# MusicVis.net
KiCad netlist of a schematic drawn in EAGLE
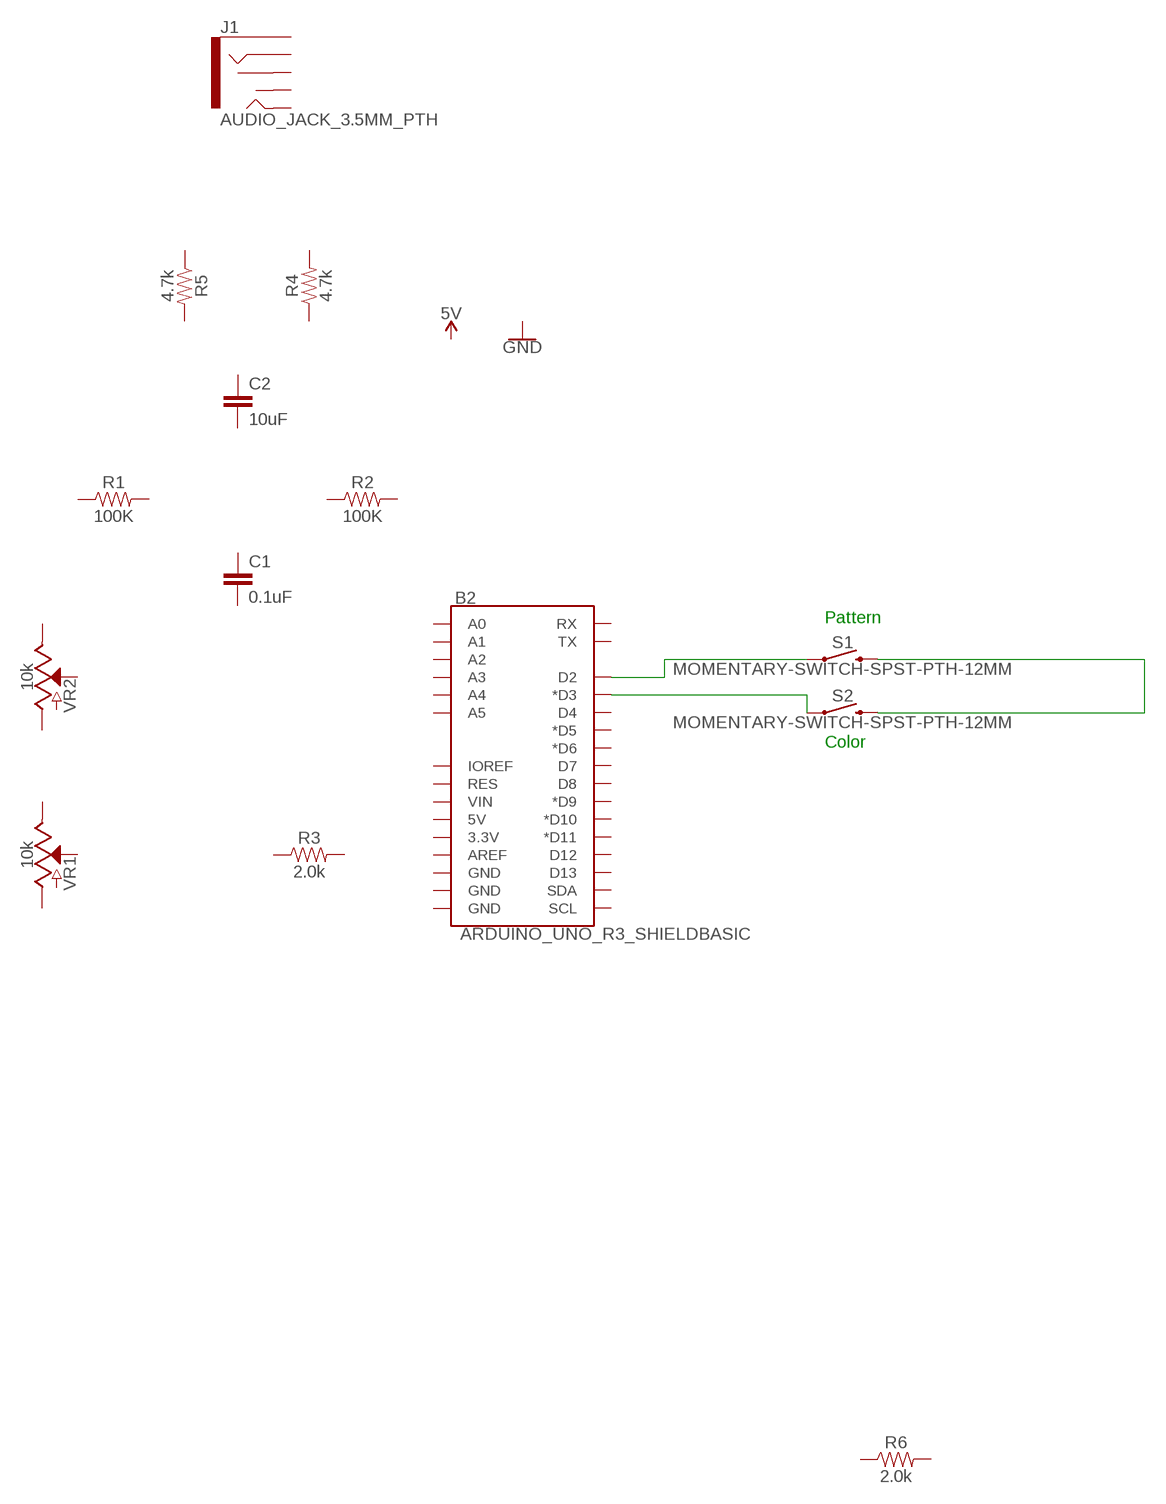
[diagram p0: schematic, sheet 1]

(export (version "E")
  (design (tool "Eeschema 10.0.6"))
  (components
    (comp (ref "B2")
      (value "ARDUINO_UNO_R3_SHIELDBASIC")
      (footprint "eagle-import:UNO_R3_SHIELD")
      (libsource (lib "eagle-import") (part "ARDUINO_UNO_R3_SHIELDBASIC"))
    )
    (comp (ref "C1")
      (value "0.1uF")
      (footprint "eagle-import:0402")
      (libsource (lib "eagle-import") (part "0.1UF-0402-16V-10%"))
    )
    (comp (ref "C2")
      (value "10uF")
      (footprint "eagle-import:0603")
      (libsource (lib "eagle-import") (part "10UF-0603-6.3V-20%"))
    )
    (comp (ref "J1")
      (value "AUDIO_JACK_3.5MM_PTH")
      (footprint "eagle-import:AUDIO-JACK")
      (libsource (lib "eagle-import") (part "AUDIO_JACK_3.5MM_PTH"))
    )
    (comp (ref "R1")
      (value "100K")
      (footprint "eagle-import:0402")
      (libsource (lib "eagle-import") (part "100KOHM-0402-1/16W-1%"))
    )
    (comp (ref "R2")
      (value "100K")
      (footprint "eagle-import:0402")
      (libsource (lib "eagle-import") (part "100KOHM-0402-1/16W-1%"))
    )
    (comp (ref "R3")
      (value "2.0k")
      (footprint "eagle-import:0603")
      (libsource (lib "eagle-import") (part "2.0KOHM-0603-1/10W-5%"))
    )
    (comp (ref "R4")
      (value "4.7k")
      (footprint "eagle-import:0603")
      (libsource (lib "eagle-import") (part "4.7KOHM-0603-1/10W-1%"))
    )
    (comp (ref "R5")
      (value "4.7k")
      (footprint "eagle-import:0603")
      (libsource (lib "eagle-import") (part "4.7KOHM-0603-1/10W-1%"))
    )
    (comp (ref "R6")
      (value "2.0k")
      (footprint "eagle-import:0603")
      (libsource (lib "eagle-import") (part "2.0KOHM-0603-1/10W-5%"))
    )
    (comp (ref "S1")
      (value "MOMENTARY-SWITCH-SPST-PTH-12MM")
      (footprint "eagle-import:TACTILE_SWITCH_PTH_12MM")
      (libsource (lib "eagle-import") (part "MOMENTARY-SWITCH-SPST-PTH-12MM"))
    )
    (comp (ref "S2")
      (value "MOMENTARY-SWITCH-SPST-PTH-12MM")
      (footprint "eagle-import:TACTILE_SWITCH_PTH_12MM")
      (libsource (lib "eagle-import") (part "MOMENTARY-SWITCH-SPST-PTH-12MM"))
    )
    (comp (ref "VR1")
      (value "10k")
      (footprint "eagle-import:POT-PTH-ALPS")
      (libsource (lib "eagle-import") (part "POTENTIOMETER-PTH-9MM-1/20W-20%"))
    )
    (comp (ref "VR2")
      (value "10k")
      (footprint "eagle-import:POT-PTH-ALPS")
      (libsource (lib "eagle-import") (part "POTENTIOMETER-PTH-9MM-1/20W-20%"))
    )
  )
  (nets
    (net (code "3") (name "Net-(B2-*D3)") (class "Default")
      (node (ref "B2") (pin "D3") (pinfunction "*D3_D3") (pintype "bidirectional"))
      (node (ref "S2") (pin "1") (pinfunction "1_1") (pintype "passive"))
    )
    (net (code "4") (name "Net-(B2-PadD2)") (class "Default")
      (node (ref "B2") (pin "D2") (pinfunction "D2_D2") (pintype "bidirectional"))
      (node (ref "S1") (pin "1") (pinfunction "1_1") (pintype "passive"))
    )
    (net (code "5") (name "Net-(S1-2)") (class "Default")
      (node (ref "S1") (pin "3") (pinfunction "2_3") (pintype "passive"))
      (node (ref "S2") (pin "3") (pinfunction "2_3") (pintype "passive"))
    )
    (net (code "6") (name "unconnected-(B2-*D5-PadD5)") (class "Default")
      (node (ref "B2") (pin "D5") (pinfunction "*D5_D5") (pintype "bidirectional"))
    )
    (net (code "7") (name "unconnected-(B2-*D6-PadD6)") (class "Default")
      (node (ref "B2") (pin "D6") (pinfunction "*D6_D6") (pintype "bidirectional"))
    )
    (net (code "8") (name "unconnected-(B2-*D9-PadD9)") (class "Default")
      (node (ref "B2") (pin "D9") (pinfunction "*D9_D9") (pintype "bidirectional"))
    )
    (net (code "9") (name "unconnected-(B2-*D10-PadD10)") (class "Default")
      (node (ref "B2") (pin "D10") (pinfunction "*D10_D10") (pintype "bidirectional"))
    )
    (net (code "10") (name "unconnected-(B2-*D11-PadD11)") (class "Default")
      (node (ref "B2") (pin "D11") (pinfunction "*D11_D11") (pintype "bidirectional"))
    )
    (net (code "11") (name "unconnected-(B2-GND-PadGND@0)") (class "Default")
      (node (ref "B2") (pin "GND@0") (pinfunction "GND_GND@0") (pintype "bidirectional"))
    )
    (net (code "12") (name "unconnected-(B2-GND-PadGND@1)") (class "Default")
      (node (ref "B2") (pin "GND@1") (pinfunction "GND_GND@1") (pintype "bidirectional"))
    )
    (net (code "13") (name "unconnected-(B2-GND-PadGND@2)") (class "Default")
      (node (ref "B2") (pin "GND@2") (pinfunction "GND_GND@2") (pintype "bidirectional"))
    )
    (net (code "14") (name "unconnected-(B2-Pad3.3V)") (class "Default")
      (node (ref "B2") (pin "3.3V") (pinfunction "3.3V_3.3V") (pintype "bidirectional"))
    )
    (net (code "15") (name "unconnected-(B2-Pad5V)") (class "Default")
      (node (ref "B2") (pin "5V") (pinfunction "5V_5V") (pintype "bidirectional"))
    )
    (net (code "16") (name "unconnected-(B2-PadA0)") (class "Default")
      (node (ref "B2") (pin "A0") (pinfunction "A0_A0") (pintype "bidirectional"))
    )
    (net (code "17") (name "unconnected-(B2-PadA1)") (class "Default")
      (node (ref "B2") (pin "A1") (pinfunction "A1_A1") (pintype "bidirectional"))
    )
    (net (code "18") (name "unconnected-(B2-PadA2)") (class "Default")
      (node (ref "B2") (pin "A2") (pinfunction "A2_A2") (pintype "bidirectional"))
    )
    (net (code "19") (name "unconnected-(B2-PadA3)") (class "Default")
      (node (ref "B2") (pin "A3") (pinfunction "A3_A3") (pintype "bidirectional"))
    )
    (net (code "20") (name "unconnected-(B2-PadA4)") (class "Default")
      (node (ref "B2") (pin "A4") (pinfunction "A4_A4") (pintype "bidirectional"))
    )
    (net (code "21") (name "unconnected-(B2-PadA5)") (class "Default")
      (node (ref "B2") (pin "A5") (pinfunction "A5_A5") (pintype "bidirectional"))
    )
    (net (code "22") (name "unconnected-(B2-PadAREF)") (class "Default")
      (node (ref "B2") (pin "AREF") (pinfunction "AREF_AREF") (pintype "bidirectional"))
    )
    (net (code "23") (name "unconnected-(B2-PadD4)") (class "Default")
      (node (ref "B2") (pin "D4") (pinfunction "D4_D4") (pintype "bidirectional"))
    )
    (net (code "24") (name "unconnected-(B2-PadD7)") (class "Default")
      (node (ref "B2") (pin "D7") (pinfunction "D7_D7") (pintype "bidirectional"))
    )
    (net (code "25") (name "unconnected-(B2-PadD8)") (class "Default")
      (node (ref "B2") (pin "D8") (pinfunction "D8_D8") (pintype "bidirectional"))
    )
    (net (code "26") (name "unconnected-(B2-PadD12)") (class "Default")
      (node (ref "B2") (pin "D12") (pinfunction "D12_D12") (pintype "bidirectional"))
    )
    (net (code "27") (name "unconnected-(B2-PadD13)") (class "Default")
      (node (ref "B2") (pin "D13") (pinfunction "D13_D13") (pintype "bidirectional"))
    )
    (net (code "28") (name "unconnected-(B2-PadIOREF)") (class "Default")
      (node (ref "B2") (pin "IOREF") (pinfunction "IOREF_IOREF") (pintype "bidirectional"))
    )
    (net (code "29") (name "unconnected-(B2-PadRES)") (class "Default")
      (node (ref "B2") (pin "RES") (pinfunction "RES_RES") (pintype "bidirectional"))
    )
    (net (code "30") (name "unconnected-(B2-PadRX)") (class "Default")
      (node (ref "B2") (pin "RX") (pinfunction "RX_RX") (pintype "bidirectional"))
    )
    (net (code "31") (name "unconnected-(B2-PadSCL)") (class "Default")
      (node (ref "B2") (pin "SCL") (pinfunction "SCL_SCL") (pintype "bidirectional"))
    )
    (net (code "32") (name "unconnected-(B2-PadSDA)") (class "Default")
      (node (ref "B2") (pin "SDA") (pinfunction "SDA_SDA") (pintype "bidirectional"))
    )
    (net (code "33") (name "unconnected-(B2-PadTX)") (class "Default")
      (node (ref "B2") (pin "TX") (pinfunction "TX_TX") (pintype "bidirectional"))
    )
    (net (code "34") (name "unconnected-(B2-PadVIN)") (class "Default")
      (node (ref "B2") (pin "VIN") (pinfunction "VIN_VIN") (pintype "bidirectional"))
    )
    (net (code "35") (name "unconnected-(C1-Pad1)") (class "Default")
      (node (ref "C1") (pin "1") (pinfunction "1_1") (pintype "passive"))
    )
    (net (code "36") (name "unconnected-(C1-Pad2)") (class "Default")
      (node (ref "C1") (pin "2") (pinfunction "2_2") (pintype "passive"))
    )
    (net (code "37") (name "unconnected-(C2-Pad1)") (class "Default")
      (node (ref "C2") (pin "1") (pinfunction "1_1") (pintype "passive"))
    )
    (net (code "38") (name "unconnected-(C2-Pad2)") (class "Default")
      (node (ref "C2") (pin "2") (pinfunction "2_2") (pintype "passive"))
    )
    (net (code "39") (name "unconnected-(J1-PadRING)") (class "Default")
      (node (ref "J1") (pin "RING") (pinfunction "RING_RING") (pintype "bidirectional"))
    )
    (net (code "40") (name "unconnected-(J1-PadRSH)") (class "Default")
      (node (ref "J1") (pin "RSH") (pinfunction "RSH_RSH") (pintype "bidirectional"))
    )
    (net (code "41") (name "unconnected-(J1-PadSLEEVE)") (class "Default")
      (node (ref "J1") (pin "SLEEVE") (pinfunction "SLEEVE_SLEEVE") (pintype "bidirectional"))
    )
    (net (code "42") (name "unconnected-(J1-PadTIP)") (class "Default")
      (node (ref "J1") (pin "TIP") (pinfunction "TIP_TIP") (pintype "bidirectional"))
    )
    (net (code "43") (name "unconnected-(J1-PadTSH)") (class "Default")
      (node (ref "J1") (pin "TSH") (pinfunction "TSH_TSH") (pintype "bidirectional"))
    )
    (net (code "44") (name "unconnected-(R1-Pad1)") (class "Default")
      (node (ref "R1") (pin "1") (pinfunction "1_1") (pintype "passive"))
    )
    (net (code "45") (name "unconnected-(R1-Pad2)") (class "Default")
      (node (ref "R1") (pin "2") (pinfunction "2_2") (pintype "passive"))
    )
    (net (code "46") (name "unconnected-(R2-Pad1)") (class "Default")
      (node (ref "R2") (pin "1") (pinfunction "1_1") (pintype "passive"))
    )
    (net (code "47") (name "unconnected-(R2-Pad2)") (class "Default")
      (node (ref "R2") (pin "2") (pinfunction "2_2") (pintype "passive"))
    )
    (net (code "48") (name "unconnected-(R3-Pad1)") (class "Default")
      (node (ref "R3") (pin "1") (pinfunction "1_1") (pintype "passive"))
    )
    (net (code "49") (name "unconnected-(R3-Pad2)") (class "Default")
      (node (ref "R3") (pin "2") (pinfunction "2_2") (pintype "passive"))
    )
    (net (code "50") (name "unconnected-(R4-Pad1)") (class "Default")
      (node (ref "R4") (pin "1") (pinfunction "1_1") (pintype "passive"))
    )
    (net (code "51") (name "unconnected-(R4-Pad2)") (class "Default")
      (node (ref "R4") (pin "2") (pinfunction "2_2") (pintype "passive"))
    )
    (net (code "52") (name "unconnected-(R5-Pad1)") (class "Default")
      (node (ref "R5") (pin "1") (pinfunction "1_1") (pintype "passive"))
    )
    (net (code "53") (name "unconnected-(R5-Pad2)") (class "Default")
      (node (ref "R5") (pin "2") (pinfunction "2_2") (pintype "passive"))
    )
    (net (code "54") (name "unconnected-(R6-Pad1)") (class "Default")
      (node (ref "R6") (pin "1") (pinfunction "1_1") (pintype "passive"))
    )
    (net (code "55") (name "unconnected-(R6-Pad2)") (class "Default")
      (node (ref "R6") (pin "2") (pinfunction "2_2") (pintype "passive"))
    )
    (net (code "56") (name "unconnected-(VR1-A-PadP$3)") (class "Default")
      (node (ref "VR1") (pin "P$3") (pinfunction "A_P$3") (pintype "passive"))
    )
    (net (code "57") (name "unconnected-(VR1-E-PadP$1)") (class "Default")
      (node (ref "VR1") (pin "P$1") (pinfunction "E_P$1") (pintype "passive"))
    )
    (net (code "58") (name "unconnected-(VR1-S-PadP$2)") (class "Default")
      (node (ref "VR1") (pin "P$2") (pinfunction "S_P$2") (pintype "passive"))
    )
    (net (code "59") (name "unconnected-(VR2-A-PadP$3)") (class "Default")
      (node (ref "VR2") (pin "P$3") (pinfunction "A_P$3") (pintype "passive"))
    )
    (net (code "60") (name "unconnected-(VR2-E-PadP$1)") (class "Default")
      (node (ref "VR2") (pin "P$1") (pinfunction "E_P$1") (pintype "passive"))
    )
    (net (code "61") (name "unconnected-(VR2-S-PadP$2)") (class "Default")
      (node (ref "VR2") (pin "P$2") (pinfunction "S_P$2") (pintype "passive"))
    )
  )
)
